# current-meter-nrf.net
KiCad netlist of a schematic drawn in EAGLE
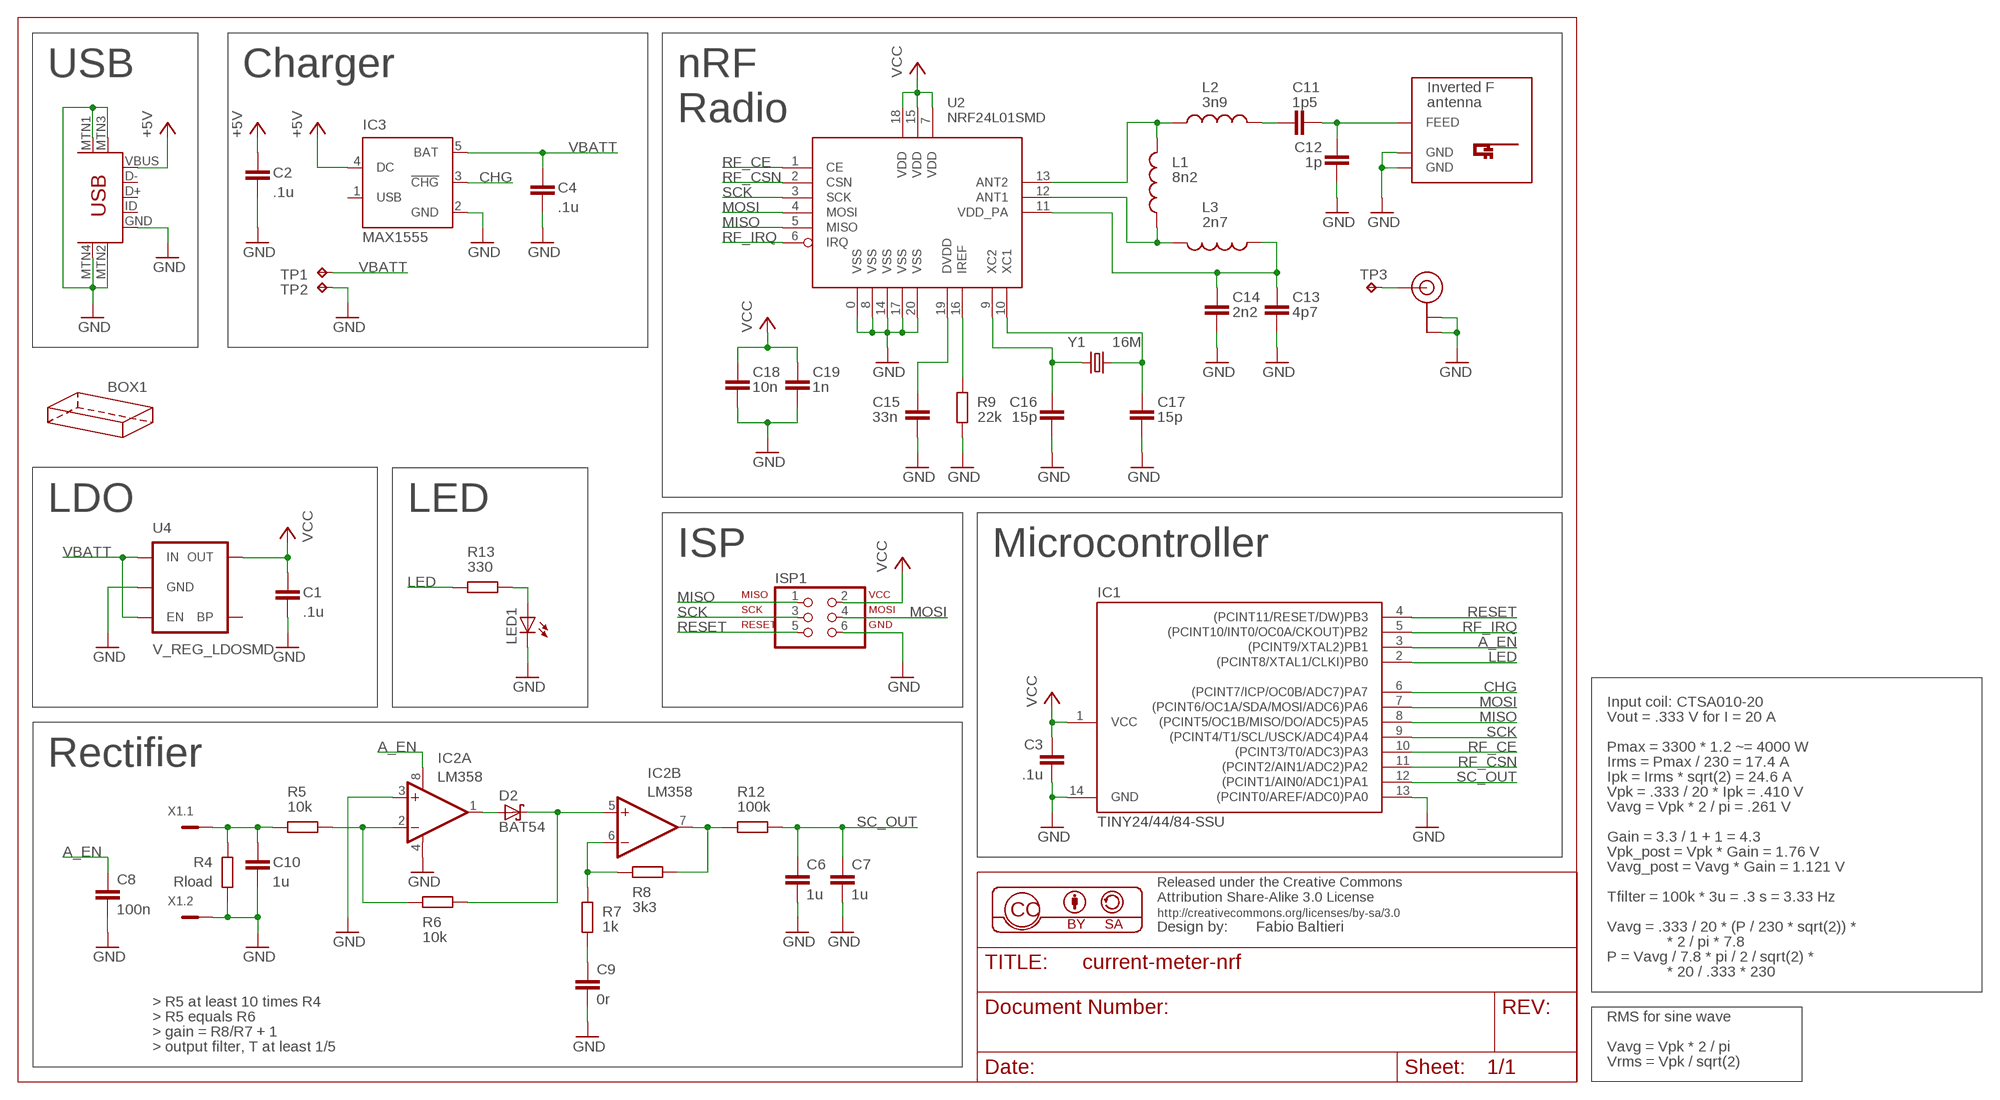
[diagram p0: schematic, sheet 1]

(export (version "E")
  (design (tool "Eeschema 10.0.6"))
  (components
    (comp (ref "BOX1")
      (value "HAMMOND-BOX-G-1H")
      (footprint "eagle-import:1551G-1HOLE")
      (libsource (lib "eagle-import") (part "HAMMOND-BOX-G-1H"))
    )
    (comp (ref "C1")
      (value ".1u")
      (footprint "eagle-import:C0805")
      (libsource (lib "eagle-import") (part "C-EUC0805"))
    )
    (comp (ref "C2")
      (value ".1u")
      (footprint "eagle-import:C0805")
      (libsource (lib "eagle-import") (part "C-EUC0805"))
    )
    (comp (ref "C3")
      (value ".1u")
      (footprint "eagle-import:C0805")
      (libsource (lib "eagle-import") (part "C-EUC0805"))
    )
    (comp (ref "C4")
      (value ".1u")
      (footprint "eagle-import:C0805")
      (libsource (lib "eagle-import") (part "C-EUC0805"))
    )
    (comp (ref "C6")
      (value "1u")
      (footprint "eagle-import:C0805")
      (libsource (lib "eagle-import") (part "C-EUC0805"))
    )
    (comp (ref "C7")
      (value "1u")
      (footprint "eagle-import:C0805")
      (libsource (lib "eagle-import") (part "C-EUC0805"))
    )
    (comp (ref "C8")
      (value "100n")
      (footprint "eagle-import:C0805")
      (libsource (lib "eagle-import") (part "C-EUC0805"))
    )
    (comp (ref "C9")
      (value "0r")
      (footprint "eagle-import:C0805")
      (libsource (lib "eagle-import") (part "C-EUC0805"))
    )
    (comp (ref "C10")
      (value "1u")
      (footprint "eagle-import:C0805")
      (libsource (lib "eagle-import") (part "C-EUC0805"))
    )
    (comp (ref "C11")
      (value "1p5")
      (footprint "eagle-import:C0603")
      (libsource (lib "eagle-import") (part "C-EUC0603"))
    )
    (comp (ref "C12")
      (value "1p")
      (footprint "eagle-import:C0603")
      (libsource (lib "eagle-import") (part "C-EUC0603"))
    )
    (comp (ref "C13")
      (value "4p7")
      (footprint "eagle-import:C0603")
      (libsource (lib "eagle-import") (part "C-EUC0603"))
    )
    (comp (ref "C14")
      (value "2n2")
      (footprint "eagle-import:C0603")
      (libsource (lib "eagle-import") (part "C-EUC0603"))
    )
    (comp (ref "C15")
      (value "33n")
      (footprint "eagle-import:C0603")
      (libsource (lib "eagle-import") (part "C-EUC0603"))
    )
    (comp (ref "C16")
      (value "15p")
      (footprint "eagle-import:C0603")
      (libsource (lib "eagle-import") (part "C-EUC0603"))
    )
    (comp (ref "C17")
      (value "15p")
      (footprint "eagle-import:C0603")
      (libsource (lib "eagle-import") (part "C-EUC0603"))
    )
    (comp (ref "C18")
      (value "10n")
      (footprint "eagle-import:C0603")
      (libsource (lib "eagle-import") (part "C-EUC0603"))
    )
    (comp (ref "C19")
      (value "1n")
      (footprint "eagle-import:C0603")
      (libsource (lib "eagle-import") (part "C-EUC0603"))
    )
    (comp (ref "D2")
      (value "BAT54")
      (footprint "eagle-import:SOT23")
      (libsource (lib "eagle-import") (part "BAT54"))
    )
    (comp (ref "IC1")
      (value "TINY24/44/84-SSU")
      (footprint "eagle-import:SOIC14")
      (libsource (lib "eagle-import") (part "TINY24/44/84-SSU"))
    )
    (comp (ref "IC2")
      (value "LM358")
      (footprint "eagle-import:SO08")
      (fields (field (name "MF") "TEXAS INSTRUMENTS") (field (name "MPN") "OPA2234U"))
      (libsource (lib "eagle-import") (part "OPA2234U"))
    )
    (comp (ref "IC3")
      (value "MAX1555")
      (footprint "eagle-import:SOT23-5L")
      (libsource (lib "eagle-import") (part "MAX1555"))
    )
    (comp (ref "ISP1")
      (value "ISP-AVR910PTH")
      (footprint "eagle-import:2X03")
      (libsource (lib "eagle-import") (part "ISP-AVR910PTH"))
    )
    (comp (ref "L1")
      (value "8n2")
      (footprint "eagle-import:0603")
      (libsource (lib "eagle-import") (part "INDUCTOR0603"))
    )
    (comp (ref "L2")
      (value "3n9")
      (footprint "eagle-import:0603")
      (libsource (lib "eagle-import") (part "INDUCTOR0603"))
    )
    (comp (ref "L3")
      (value "2n7")
      (footprint "eagle-import:0603")
      (libsource (lib "eagle-import") (part "INDUCTOR0603"))
    )
    (comp (ref "LED1")
      (value "LEDSML0805")
      (footprint "eagle-import:SML0805")
      (libsource (lib "eagle-import") (part "LEDSML0805"))
    )
    (comp (ref "R4")
      (value "Rload")
      (footprint "eagle-import:R0805")
      (libsource (lib "eagle-import") (part "R-EU_R0805"))
    )
    (comp (ref "R5")
      (value "10k")
      (footprint "eagle-import:R0603")
      (libsource (lib "eagle-import") (part "R-EU_R0603"))
    )
    (comp (ref "R6")
      (value "10k")
      (footprint "eagle-import:R0603")
      (libsource (lib "eagle-import") (part "R-EU_R0603"))
    )
    (comp (ref "R7")
      (value "1k")
      (footprint "eagle-import:R0603")
      (libsource (lib "eagle-import") (part "R-EU_R0603"))
    )
    (comp (ref "R8")
      (value "3k3")
      (footprint "eagle-import:R0603")
      (libsource (lib "eagle-import") (part "R-EU_R0603"))
    )
    (comp (ref "R9")
      (value "22k")
      (footprint "eagle-import:R0603")
      (libsource (lib "eagle-import") (part "R-EU_R0603"))
    )
    (comp (ref "R12")
      (value "100k")
      (footprint "eagle-import:R0603")
      (libsource (lib "eagle-import") (part "R-EU_R0603"))
    )
    (comp (ref "R13")
      (value "330")
      (footprint "eagle-import:R0603")
      (libsource (lib "eagle-import") (part "R-EU_R0603"))
    )
    (comp (ref "TP1")
      (value "TPTP12R")
      (footprint "eagle-import:TP12R")
      (libsource (lib "eagle-import") (part "TPTP12R"))
    )
    (comp (ref "TP2")
      (value "TPTP12R")
      (footprint "eagle-import:TP12R")
      (libsource (lib "eagle-import") (part "TPTP12R"))
    )
    (comp (ref "TP3")
      (value "TPTP08SQ")
      (footprint "eagle-import:TP08SQ")
      (libsource (lib "eagle-import") (part "TPTP08SQ"))
    )
    (comp (ref "U$1")
      (value "INVERTED_F_ANTENNA+5")
      (footprint "eagle-import:DN007+5")
      (libsource (lib "eagle-import") (part "INVERTED_F_ANTENNA+5"))
    )
    (comp (ref "U$2")
      (value "U.FL")
      (footprint "eagle-import:U.FL")
      (libsource (lib "eagle-import") (part "U.FL"))
    )
    (comp (ref "U2")
      (value "NRF24L01SMD")
      (footprint "eagle-import:QFN20")
      (libsource (lib "eagle-import") (part "NRF24L01SMD"))
    )
    (comp (ref "U3")
      (value "USB-MINIB-5PIN")
      (footprint "eagle-import:USB-MINIB")
      (libsource (lib "eagle-import") (part "USB-MINIB-5PIN"))
    )
    (comp (ref "U4")
      (value "V_REG_LDOSMD")
      (footprint "eagle-import:SOT23-5")
      (libsource (lib "eagle-import") (part "V_REG_LDOSMD"))
    )
    (comp (ref "X1")
      (value "MC2")
      (footprint "eagle-import:MC2")
      (libsource (lib "eagle-import") (part "MC2"))
    )
    (comp (ref "Y1")
      (value "16M")
      (footprint "eagle-import:CRYSTAL-SMD-5X3")
      (libsource (lib "eagle-import") (part "CRYSTAL5X3"))
    )
  )
  (nets
    (net (code "1") (name "+5V") (class "Default")
      (node (ref "C2") (pin "1") (pinfunction "1_1") (pintype "passive"))
      (node (ref "IC3") (pin "4") (pinfunction "DC_4") (pintype "input"))
      (node (ref "U3") (pin "VBUS") (pinfunction "VBUS_VBUS") (pintype "bidirectional"))
    )
    (net (code "2") (name "/A_EN") (class "Default")
      (node (ref "C8") (pin "1") (pinfunction "1_1") (pintype "passive"))
      (node (ref "IC1") (pin "3") (pinfunction "(PCINT9/XTAL2)PB1_3") (pintype "bidirectional"))
      (node (ref "IC2") (pin "8") (pinfunction "V+_8") (pintype "power_in"))
    )
    (net (code "3") (name "/CHG") (class "Default")
      (node (ref "IC1") (pin "6") (pinfunction "(PCINT7/ICP/OC0B/ADC7)PA7_6") (pintype "bidirectional"))
      (node (ref "IC3") (pin "3") (pinfunction "~{CHG}_3") (pintype "output"))
    )
    (net (code "4") (name "/LED") (class "Default")
      (node (ref "IC1") (pin "2") (pinfunction "(PCINT8/XTAL1/CLKI)PB0_2") (pintype "bidirectional"))
      (node (ref "R13") (pin "2") (pinfunction "2_2") (pintype "passive"))
    )
    (net (code "5") (name "/MISO") (class "Default")
      (node (ref "IC1") (pin "8") (pinfunction "(PCINT5/OC1B/MISO/DO/ADC5)PA5_8") (pintype "bidirectional"))
      (node (ref "ISP1") (pin "1") (pinfunction "1_1") (pintype "passive"))
      (node (ref "U2") (pin "5") (pinfunction "MISO_5") (pintype "output"))
    )
    (net (code "6") (name "/MOSI") (class "Default")
      (node (ref "IC1") (pin "7") (pinfunction "(PCINT6/OC1A/SDA/MOSI/ADC6)PA6_7") (pintype "bidirectional"))
      (node (ref "ISP1") (pin "4") (pinfunction "4_4") (pintype "passive"))
      (node (ref "U2") (pin "4") (pinfunction "MOSI_4") (pintype "input"))
    )
    (net (code "7") (name "/RESET") (class "Default")
      (node (ref "IC1") (pin "4") (pinfunction "(PCINT11/RESET/DW)PB3_4") (pintype "bidirectional"))
      (node (ref "ISP1") (pin "5") (pinfunction "5_5") (pintype "passive"))
    )
    (net (code "8") (name "/RF_CE") (class "Default")
      (node (ref "IC1") (pin "10") (pinfunction "(PCINT3/T0/ADC3)PA3_10") (pintype "bidirectional"))
      (node (ref "U2") (pin "1") (pinfunction "CE_1") (pintype "input"))
    )
    (net (code "9") (name "/RF_CSN") (class "Default")
      (node (ref "IC1") (pin "11") (pinfunction "(PCINT2/AIN1/ADC2)PA2_11") (pintype "bidirectional"))
      (node (ref "U2") (pin "2") (pinfunction "CSN_2") (pintype "input"))
    )
    (net (code "10") (name "/RF_IRQ") (class "Default")
      (node (ref "IC1") (pin "5") (pinfunction "(PCINT10/INT0/OC0A/CKOUT)PB2_5") (pintype "bidirectional"))
      (node (ref "U2") (pin "6") (pinfunction "IRQ_6") (pintype "output"))
    )
    (net (code "11") (name "/SCK") (class "Default")
      (node (ref "IC1") (pin "9") (pinfunction "(PCINT4/T1/SCL/USCK/ADC4)PA4_9") (pintype "bidirectional"))
      (node (ref "ISP1") (pin "3") (pinfunction "3_3") (pintype "passive"))
      (node (ref "U2") (pin "3") (pinfunction "SCK_3") (pintype "input"))
    )
    (net (code "12") (name "/SC_OUT") (class "Default")
      (node (ref "C6") (pin "1") (pinfunction "1_1") (pintype "passive"))
      (node (ref "C7") (pin "1") (pinfunction "1_1") (pintype "passive"))
      (node (ref "IC1") (pin "12") (pinfunction "(PCINT1/AIN0/ADC1)PA1_12") (pintype "bidirectional"))
      (node (ref "R12") (pin "2") (pinfunction "2_2") (pintype "passive"))
    )
    (net (code "13") (name "/VBATT") (class "Default")
      (node (ref "C4") (pin "1") (pinfunction "1_1") (pintype "passive"))
      (node (ref "IC3") (pin "5") (pinfunction "BAT_5") (pintype "passive"))
      (node (ref "TP1") (pin "TP") (pinfunction "TP_TP") (pintype "input"))
      (node (ref "U4") (pin "1") (pinfunction "IN_1") (pintype "input"))
      (node (ref "U4") (pin "3") (pinfunction "EN_3") (pintype "input"))
    )
    (net (code "14") (name "GND") (class "Default")
      (node (ref "C1") (pin "2") (pinfunction "2_2") (pintype "passive"))
      (node (ref "C10") (pin "2") (pinfunction "2_2") (pintype "passive"))
      (node (ref "C12") (pin "2") (pinfunction "2_2") (pintype "passive"))
      (node (ref "C13") (pin "2") (pinfunction "2_2") (pintype "passive"))
      (node (ref "C14") (pin "2") (pinfunction "2_2") (pintype "passive"))
      (node (ref "C15") (pin "2") (pinfunction "2_2") (pintype "passive"))
      (node (ref "C16") (pin "2") (pinfunction "2_2") (pintype "passive"))
      (node (ref "C17") (pin "2") (pinfunction "2_2") (pintype "passive"))
      (node (ref "C18") (pin "2") (pinfunction "2_2") (pintype "passive"))
      (node (ref "C19") (pin "2") (pinfunction "2_2") (pintype "passive"))
      (node (ref "C2") (pin "2") (pinfunction "2_2") (pintype "passive"))
      (node (ref "C3") (pin "2") (pinfunction "2_2") (pintype "passive"))
      (node (ref "C4") (pin "2") (pinfunction "2_2") (pintype "passive"))
      (node (ref "C6") (pin "2") (pinfunction "2_2") (pintype "passive"))
      (node (ref "C7") (pin "2") (pinfunction "2_2") (pintype "passive"))
      (node (ref "C8") (pin "2") (pinfunction "2_2") (pintype "passive"))
      (node (ref "C9") (pin "2") (pinfunction "2_2") (pintype "passive"))
      (node (ref "IC1") (pin "13") (pinfunction "(PCINT0/AREF/ADC0)PA0_13") (pintype "bidirectional"))
      (node (ref "IC1") (pin "14") (pinfunction "GND_14") (pintype "power_in"))
      (node (ref "IC2") (pin "3") (pinfunction "+IN_3") (pintype "input"))
      (node (ref "IC2") (pin "4") (pinfunction "V-_4") (pintype "power_in"))
      (node (ref "IC3") (pin "2") (pinfunction "GND_2") (pintype "power_in"))
      (node (ref "ISP1") (pin "6") (pinfunction "6_6") (pintype "passive"))
      (node (ref "LED1") (pin "C") (pinfunction "C_C") (pintype "passive"))
      (node (ref "R4") (pin "1") (pinfunction "1_1") (pintype "passive"))
      (node (ref "R9") (pin "2") (pinfunction "2_2") (pintype "passive"))
      (node (ref "TP2") (pin "TP") (pinfunction "TP_TP") (pintype "input"))
      (node (ref "U$1") (pin "GND") (pinfunction "GND_GND") (pintype "bidirectional"))
      (node (ref "U$1") (pin "GND@1") (pinfunction "GND_GND@1") (pintype "bidirectional"))
      (node (ref "U$2") (pin "P$1") (pinfunction "GND_P$1") (pintype "bidirectional"))
      (node (ref "U$2") (pin "P$2") (pinfunction "GND_P$2") (pintype "bidirectional"))
      (node (ref "U2") (pin "0") (pinfunction "VSS_0") (pintype "power_in"))
      (node (ref "U2") (pin "14") (pinfunction "VSS_14") (pintype "power_in"))
      (node (ref "U2") (pin "17") (pinfunction "VSS_17") (pintype "power_in"))
      (node (ref "U2") (pin "20") (pinfunction "VSS_20") (pintype "power_in"))
      (node (ref "U2") (pin "8") (pinfunction "VSS_8") (pintype "power_in"))
      (node (ref "U3") (pin "GND") (pinfunction "GND_GND") (pintype "bidirectional"))
      (node (ref "U3") (pin "MTN1") (pinfunction "MTN2_MTN1") (pintype "bidirectional"))
      (node (ref "U3") (pin "MTN2") (pinfunction "MTN3_MTN2") (pintype "bidirectional"))
      (node (ref "U3") (pin "MTN3") (pinfunction "MTN1_MTN3") (pintype "bidirectional"))
      (node (ref "U3") (pin "MTN4") (pinfunction "MTN4_MTN4") (pintype "bidirectional"))
      (node (ref "U4") (pin "2") (pinfunction "GND_2") (pintype "input"))
      (node (ref "X1") (pin "2") (pinfunction "SK_2") (pintype "passive"))
    )
    (net (code "15") (name "Net-(C9-Pad1)") (class "Default")
      (node (ref "C9") (pin "1") (pinfunction "1_1") (pintype "passive"))
      (node (ref "R7") (pin "1") (pinfunction "1_1") (pintype "passive"))
    )
    (net (code "16") (name "Net-(C11-Pad1)") (class "Default")
      (node (ref "C11") (pin "1") (pinfunction "1_1") (pintype "passive"))
      (node (ref "L2") (pin "2") (pinfunction "2_2") (pintype "passive"))
    )
    (net (code "17") (name "Net-(C11-Pad2)") (class "Default")
      (node (ref "C11") (pin "2") (pinfunction "2_2") (pintype "passive"))
      (node (ref "C12") (pin "1") (pinfunction "1_1") (pintype "passive"))
      (node (ref "U$1") (pin "FEED") (pinfunction "FEED_FEED") (pintype "bidirectional"))
    )
    (net (code "18") (name "Net-(D2-A)") (class "Default")
      (node (ref "D2") (pin "1") (pinfunction "A_1") (pintype "passive"))
      (node (ref "IC2") (pin "1") (pinfunction "OUT_1") (pintype "output"))
    )
    (net (code "19") (name "Net-(D2-C)") (class "Default")
      (node (ref "D2") (pin "3") (pinfunction "C_3") (pintype "passive"))
      (node (ref "IC2") (pin "5") (pinfunction "+IN_5") (pintype "input"))
      (node (ref "R6") (pin "2") (pinfunction "2_2") (pintype "passive"))
    )
    (net (code "20") (name "Net-(IC2A--IN)") (class "Default")
      (node (ref "IC2") (pin "2") (pinfunction "-IN_2") (pintype "input"))
      (node (ref "R5") (pin "2") (pinfunction "2_2") (pintype "passive"))
      (node (ref "R6") (pin "1") (pinfunction "1_1") (pintype "passive"))
    )
    (net (code "21") (name "Net-(IC2B--IN)") (class "Default")
      (node (ref "IC2") (pin "6") (pinfunction "-IN_6") (pintype "input"))
      (node (ref "R7") (pin "2") (pinfunction "2_2") (pintype "passive"))
      (node (ref "R8") (pin "1") (pinfunction "1_1") (pintype "passive"))
    )
    (net (code "22") (name "Net-(IC2B-OUT)") (class "Default")
      (node (ref "IC2") (pin "7") (pinfunction "OUT_7") (pintype "output"))
      (node (ref "R12") (pin "1") (pinfunction "1_1") (pintype "passive"))
      (node (ref "R8") (pin "2") (pinfunction "2_2") (pintype "passive"))
    )
    (net (code "23") (name "Net-(LED1-PadA)") (class "Default")
      (node (ref "LED1") (pin "A") (pinfunction "A_A") (pintype "passive"))
      (node (ref "R13") (pin "1") (pinfunction "1_1") (pintype "passive"))
    )
    (net (code "24") (name "Net-(U$2-SIGNAL)") (class "Default")
      (node (ref "TP3") (pin "TP") (pinfunction "TP_TP") (pintype "input"))
      (node (ref "U$2") (pin "P$3") (pinfunction "SIGNAL_P$3") (pintype "bidirectional"))
    )
    (net (code "25") (name "Net-(U2-ANT1)") (class "Default")
      (node (ref "L1") (pin "2") (pinfunction "2_2") (pintype "passive"))
      (node (ref "L3") (pin "2") (pinfunction "2_2") (pintype "passive"))
      (node (ref "U2") (pin "12") (pinfunction "ANT1_12") (pintype "output"))
    )
    (net (code "26") (name "Net-(U2-ANT2)") (class "Default")
      (node (ref "L1") (pin "1") (pinfunction "1_1") (pintype "passive"))
      (node (ref "L2") (pin "1") (pinfunction "1_1") (pintype "passive"))
      (node (ref "U2") (pin "13") (pinfunction "ANT2_13") (pintype "output"))
    )
    (net (code "27") (name "Net-(U2-DVDD)") (class "Default")
      (node (ref "C15") (pin "1") (pinfunction "1_1") (pintype "passive"))
      (node (ref "U2") (pin "19") (pinfunction "DVDD_19") (pintype "power_in"))
    )
    (net (code "28") (name "Net-(U2-IREF)") (class "Default")
      (node (ref "R9") (pin "1") (pinfunction "1_1") (pintype "passive"))
      (node (ref "U2") (pin "16") (pinfunction "IREF_16") (pintype "input"))
    )
    (net (code "29") (name "Net-(U2-VDD_PA)") (class "Default")
      (node (ref "C13") (pin "1") (pinfunction "1_1") (pintype "passive"))
      (node (ref "C14") (pin "1") (pinfunction "1_1") (pintype "passive"))
      (node (ref "L3") (pin "1") (pinfunction "1_1") (pintype "passive"))
      (node (ref "U2") (pin "11") (pinfunction "VDD_PA_11") (pintype "power_in"))
    )
    (net (code "30") (name "Net-(U2-XC1)") (class "Default")
      (node (ref "C17") (pin "1") (pinfunction "1_1") (pintype "passive"))
      (node (ref "U2") (pin "10") (pinfunction "XC1_10") (pintype "input"))
      (node (ref "Y1") (pin "3") (pinfunction "2_3") (pintype "passive"))
    )
    (net (code "31") (name "Net-(U2-XC2)") (class "Default")
      (node (ref "C16") (pin "1") (pinfunction "1_1") (pintype "passive"))
      (node (ref "U2") (pin "9") (pinfunction "XC2_9") (pintype "input"))
      (node (ref "Y1") (pin "1") (pinfunction "1_1") (pintype "passive"))
    )
    (net (code "32") (name "Net-(X1A-SK)") (class "Default")
      (node (ref "C10") (pin "1") (pinfunction "1_1") (pintype "passive"))
      (node (ref "R4") (pin "2") (pinfunction "2_2") (pintype "passive"))
      (node (ref "R5") (pin "1") (pinfunction "1_1") (pintype "passive"))
      (node (ref "X1") (pin "1") (pinfunction "SK_1") (pintype "passive"))
    )
    (net (code "33") (name "VCC") (class "Default")
      (node (ref "C1") (pin "1") (pinfunction "1_1") (pintype "passive"))
      (node (ref "C18") (pin "1") (pinfunction "1_1") (pintype "passive"))
      (node (ref "C19") (pin "1") (pinfunction "1_1") (pintype "passive"))
      (node (ref "C3") (pin "1") (pinfunction "1_1") (pintype "passive"))
      (node (ref "IC1") (pin "1") (pinfunction "VCC_1") (pintype "power_in"))
      (node (ref "ISP1") (pin "2") (pinfunction "2_2") (pintype "passive"))
      (node (ref "U2") (pin "15") (pinfunction "VDD_15") (pintype "power_in"))
      (node (ref "U2") (pin "18") (pinfunction "VDD_18") (pintype "power_in"))
      (node (ref "U2") (pin "7") (pinfunction "VDD_7") (pintype "power_in"))
      (node (ref "U4") (pin "5") (pinfunction "OUT_5") (pintype "passive"))
    )
    (net (code "34") (name "unconnected-(IC3-USB-Pad1)") (class "Default")
      (node (ref "IC3") (pin "1") (pinfunction "USB_1") (pintype "input"))
    )
    (net (code "35") (name "unconnected-(U3-PadD+)") (class "Default")
      (node (ref "U3") (pin "D+") (pinfunction "D+_D+") (pintype "bidirectional"))
    )
    (net (code "36") (name "unconnected-(U3-PadD-)") (class "Default")
      (node (ref "U3") (pin "D-") (pinfunction "D-_D-") (pintype "bidirectional"))
    )
    (net (code "37") (name "unconnected-(U3-PadID)") (class "Default")
      (node (ref "U3") (pin "ID") (pinfunction "ID_ID") (pintype "bidirectional"))
    )
    (net (code "38") (name "unconnected-(U4-BP-Pad4)") (class "Default")
      (node (ref "U4") (pin "4") (pinfunction "BP_4") (pintype "input"))
    )
  )
)
